# driver-ha-v1.net
KiCad netlist of a schematic drawn in EAGLE
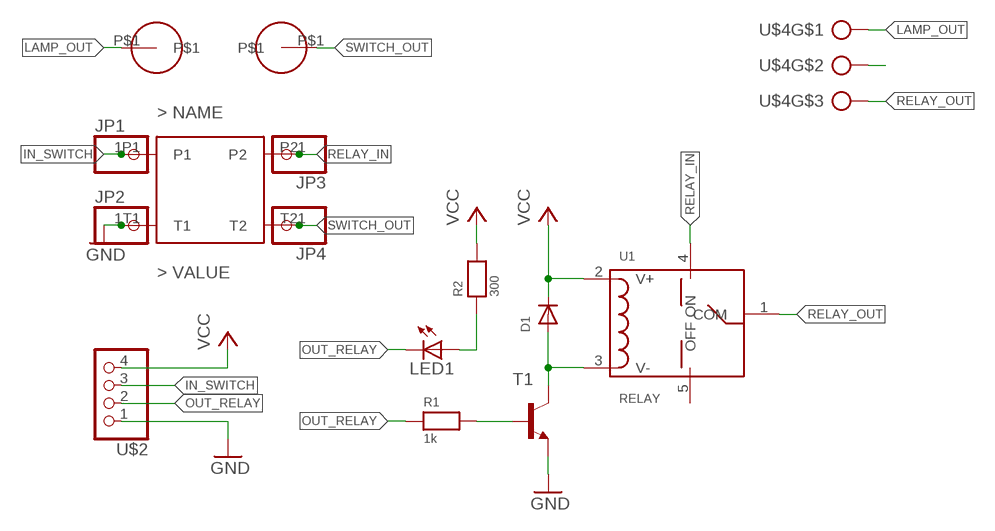
[diagram p0: schematic, sheet 1]

(export (version "E")
  (design (tool "Eeschema 10.0.6"))
  (components
    (comp (ref "D1")
      (value "DIODESMA")
      (footprint "eagle-import:SMADIODE")
      (libsource (lib "eagle-import") (part "DIODESMA"))
    )
    (comp (ref "JP1")
      (value "PINHD-1X1")
      (footprint "eagle-import:1X01")
      (libsource (lib "eagle-import") (part "PINHD-1X1"))
    )
    (comp (ref "JP2")
      (value "PINHD-1X1")
      (footprint "eagle-import:1X01")
      (libsource (lib "eagle-import") (part "PINHD-1X1"))
    )
    (comp (ref "JP3")
      (value "PINHD-1X1")
      (footprint "eagle-import:1X01")
      (libsource (lib "eagle-import") (part "PINHD-1X1"))
    )
    (comp (ref "JP4")
      (value "PINHD-1X1")
      (footprint "eagle-import:1X01")
      (libsource (lib "eagle-import") (part "PINHD-1X1"))
    )
    (comp (ref "LED1")
      (value "LEDCHIPLED_0805")
      (footprint "eagle-import:CHIPLED_0805")
      (libsource (lib "eagle-import") (part "LEDCHIPLED_0805"))
    )
    (comp (ref "R1")
      (value "1k")
      (footprint "eagle-import:0603")
      (libsource (lib "eagle-import") (part "RESISTOR0603"))
    )
    (comp (ref "R2")
      (value "300")
      (footprint "eagle-import:0603")
      (libsource (lib "eagle-import") (part "RESISTOR0603"))
    )
    (comp (ref "ROOM_SWITCH")
      (value "DPST-SWITCH-1221")
      (footprint "eagle-import:TOGGLE-SW-E1221")
      (libsource (lib "eagle-import") (part "DPST-SWITCH-1221"))
    )
    (comp (ref "T1")
      (value "MMBT2222ALT1-NPN-SOT23-BEC")
      (footprint "eagle-import:SOT23-BEC")
      (libsource (lib "eagle-import") (part "-NPN-SOT23-BECMMBT2222ALT1"))
    )
    (comp (ref "U$1")
      (value "CONN-CABLE")
      (footprint "eagle-import:CONN-CABLE")
      (libsource (lib "eagle-import") (part "CONN-CABLE"))
    )
    (comp (ref "U$2")
      (value "HEADER-1X4")
      (footprint "eagle-import:1X04_OVAL")
      (libsource (lib "eagle-import") (part "HEADER-1X4"))
    )
    (comp (ref "U$3")
      (value "CONN-CABLE")
      (footprint "eagle-import:CONN-CABLE")
      (libsource (lib "eagle-import") (part "CONN-CABLE"))
    )
    (comp (ref "U$4")
      (value "AK3003")
      (footprint "eagle-import:AK3003")
      (libsource (lib "eagle-import") (part "AK3003"))
    )
    (comp (ref "U1")
      (value "RELAY")
      (footprint "eagle-import:RELAY")
      (libsource (lib "eagle-import") (part "RELAY"))
    )
  )
  (nets
    (net (code "1") (name "GND") (class "Default")
      (node (ref "JP2") (pin "1") (pinfunction "1_1") (pintype "passive"))
      (node (ref "ROOM_SWITCH") (pin "T1") (pinfunction "T1_T1") (pintype "bidirectional"))
      (node (ref "T1") (pin "E") (pinfunction "E_E") (pintype "passive"))
      (node (ref "U$2") (pin "1") (pinfunction "1_1") (pintype "passive"))
    )
    (net (code "2") (name "IN_SWITCH") (class "Default")
      (node (ref "JP1") (pin "1") (pinfunction "1_1") (pintype "passive"))
      (node (ref "ROOM_SWITCH") (pin "P1") (pinfunction "P1_P1") (pintype "bidirectional"))
      (node (ref "U$2") (pin "3") (pinfunction "3_3") (pintype "passive"))
    )
    (net (code "3") (name "LAMP_OUT") (class "Default")
      (node (ref "U$1") (pin "P$1") (pinfunction "P$1_P$1") (pintype "bidirectional"))
      (node (ref "U$4") (pin "1") (pinfunction "KL_1") (pintype "passive"))
    )
    (net (code "4") (name "Net-(LED1-PadA)") (class "Default")
      (node (ref "LED1") (pin "A") (pinfunction "A_A") (pintype "passive"))
      (node (ref "R2") (pin "1") (pinfunction "1_1") (pintype "passive"))
    )
    (net (code "5") (name "Net-(R1-Pad2)") (class "Default")
      (node (ref "R1") (pin "2") (pinfunction "2_2") (pintype "passive"))
      (node (ref "T1") (pin "B") (pinfunction "B_B") (pintype "passive"))
    )
    (net (code "6") (name "Net-(U1-V-)") (class "Default")
      (node (ref "D1") (pin "A") (pinfunction "A_A") (pintype "passive"))
      (node (ref "T1") (pin "C") (pinfunction "C_C") (pintype "passive"))
      (node (ref "U1") (pin "3") (pinfunction "V-_3") (pintype "bidirectional"))
    )
    (net (code "7") (name "OUT_RELAY") (class "Default")
      (node (ref "LED1") (pin "C") (pinfunction "C_C") (pintype "passive"))
      (node (ref "R1") (pin "1") (pinfunction "1_1") (pintype "passive"))
      (node (ref "U$2") (pin "2") (pinfunction "2_2") (pintype "passive"))
    )
    (net (code "8") (name "RELAY_IN") (class "Default")
      (node (ref "JP3") (pin "1") (pinfunction "1_1") (pintype "passive"))
      (node (ref "ROOM_SWITCH") (pin "P2") (pinfunction "P2_P2") (pintype "bidirectional"))
      (node (ref "U1") (pin "4") (pinfunction "ON_4") (pintype "bidirectional"))
    )
    (net (code "9") (name "RELAY_OUT") (class "Default")
      (node (ref "U$4") (pin "3") (pinfunction "KL_3") (pintype "passive"))
      (node (ref "U1") (pin "1") (pinfunction "COM_1") (pintype "bidirectional"))
    )
    (net (code "10") (name "SWITCH_OUT") (class "Default")
      (node (ref "JP4") (pin "1") (pinfunction "1_1") (pintype "passive"))
      (node (ref "ROOM_SWITCH") (pin "T2") (pinfunction "T2_T2") (pintype "bidirectional"))
      (node (ref "U$3") (pin "P$1") (pinfunction "P$1_P$1") (pintype "bidirectional"))
    )
    (net (code "11") (name "VCC") (class "Default")
      (node (ref "D1") (pin "C") (pinfunction "C_C") (pintype "passive"))
      (node (ref "R2") (pin "2") (pinfunction "2_2") (pintype "passive"))
      (node (ref "U$2") (pin "4") (pinfunction "4_4") (pintype "passive"))
      (node (ref "U1") (pin "2") (pinfunction "V+_2") (pintype "bidirectional"))
    )
    (net (code "12") (name "unconnected-(U$4B-KL-Pad2)") (class "Default")
      (node (ref "U$4") (pin "2") (pinfunction "KL_2") (pintype "passive"))
    )
    (net (code "13") (name "unconnected-(U1-OFF-Pad5)") (class "Default")
      (node (ref "U1") (pin "5") (pinfunction "OFF_5") (pintype "bidirectional"))
    )
  )
)
